# Leds.net
KiCad netlist of a schematic drawn in EAGLE
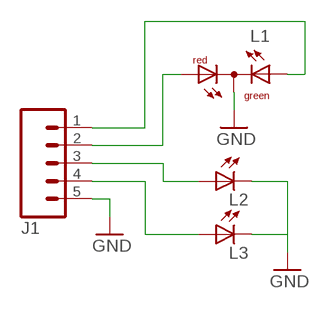
[diagram p0: schematic, sheet 1]

(export (version "E")
  (design (tool "Eeschema 10.0.6"))
  (components
    (comp (ref "J1")
      (value "M05PTH")
      (footprint "eagle-import:1X05")
      (libsource (lib "eagle-import") (part "M05PTH"))
    )
    (comp (ref "L1")
      (value "DUOLED-RG-C")
      (footprint "eagle-import:DUOLED-C-5MM")
      (libsource (lib "eagle-import") (part "DUOLED-RG-C"))
    )
    (comp (ref "L2")
      (value "LED3MM")
      (footprint "eagle-import:LED3MM")
      (libsource (lib "eagle-import") (part "LED3MM"))
    )
    (comp (ref "L3")
      (value "LED3MM")
      (footprint "eagle-import:LED3MM")
      (libsource (lib "eagle-import") (part "LED3MM"))
    )
  )
  (nets
    (net (code "1") (name "GND") (class "Default")
      (node (ref "J1") (pin "5") (pinfunction "5_5") (pintype "passive"))
      (node (ref "L1") (pin "C") (pinfunction "C_C") (pintype "passive"))
      (node (ref "L2") (pin "K") (pinfunction "C_K") (pintype "passive"))
      (node (ref "L3") (pin "K") (pinfunction "C_K") (pintype "passive"))
    )
    (net (code "2") (name "Net-(J1-Pad2)") (class "Default")
      (node (ref "J1") (pin "2") (pinfunction "2_2") (pintype "passive"))
      (node (ref "L1") (pin "AR") (pinfunction "AR_AR") (pintype "passive"))
    )
    (net (code "3") (name "Net-(J1-Pad3)") (class "Default")
      (node (ref "J1") (pin "3") (pinfunction "3_3") (pintype "passive"))
      (node (ref "L2") (pin "A") (pinfunction "A_A") (pintype "passive"))
    )
    (net (code "4") (name "Net-(J1-Pad4)") (class "Default")
      (node (ref "J1") (pin "4") (pinfunction "4_4") (pintype "passive"))
      (node (ref "L3") (pin "A") (pinfunction "A_A") (pintype "passive"))
    )
    (net (code "5") (name "Net-(L1-AG)") (class "Default")
      (node (ref "J1") (pin "1") (pinfunction "1_1") (pintype "passive"))
      (node (ref "L1") (pin "AX") (pinfunction "AG_AX") (pintype "passive"))
    )
  )
)
